# ideal-diode.net
KiCad netlist of a schematic drawn in Altium Designer
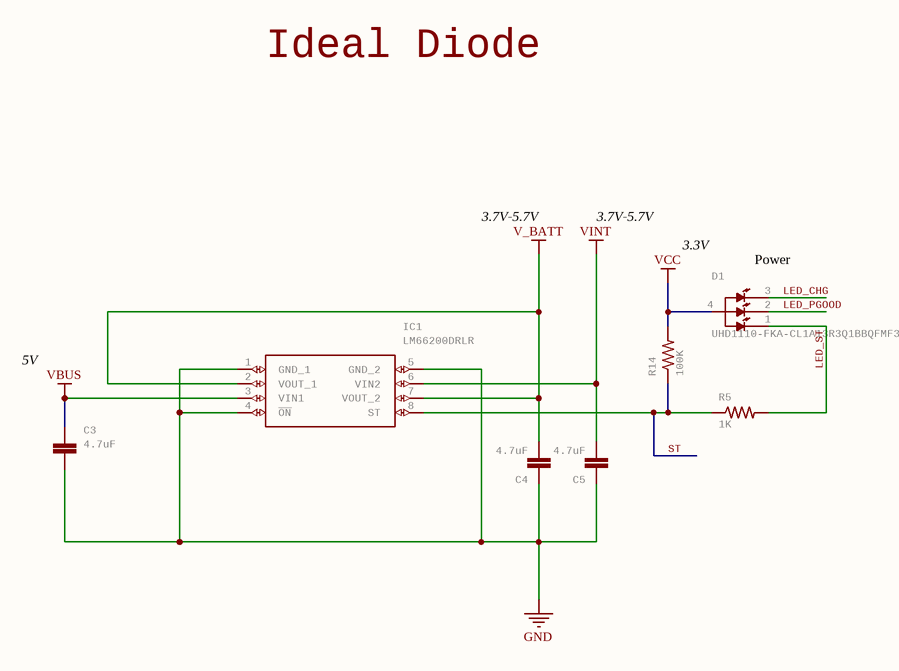
[diagram p0: ideal-diode.SchDoc]

(export (version "E")
  (design (tool "Eeschema 10.0.6"))
  (components
    (comp (ref "C3")
      (value "4.7uF")
      (footprint "0402-CAP")
      (description "CapacitorStandard 0603 ceramic capacitor, and 0.1\" leaded capacitor.")
      (fields (field (name "MPN") "JMK105BBJ475MV-F"))
      (libsource (lib "rt10") (part "CAP0402-CAP"))
    )
    (comp (ref "C4")
      (value "4.7uF")
      (footprint "0402-CAP")
      (description "CapacitorStandard 0603 ceramic capacitor, and 0.1\" leaded capacitor.")
      (fields (field (name "MPN") "JMK105BBJ475MV-F"))
      (libsource (lib "rt10") (part "CAP0402-CAP"))
    )
    (comp (ref "C5")
      (value "4.7uF")
      (footprint "0402-CAP")
      (description "CapacitorStandard 0603 ceramic capacitor, and 0.1\" leaded capacitor.")
      (fields (field (name "MPN") "JMK105BBJ475MV-F"))
      (libsource (lib "rt10") (part "CAP0402-CAP"))
    )
    (comp (ref "D1")
      (value "UHD1110-FKA-CL1A13R3Q1BBQFMF3")
      (footprint "LED_UHD1110-FKA-CL1A13R3Q1BBQFMF3")
      (description "LED RGB SMD, SIZE 1 X 1 mm Check availability")
      (fields (field (name "MF") "Cree Inc.") (field (name "MPN") "UHD1110-FKA-CL1A13r3q1BBQFMF3"))
      (libsource (lib "rt10") (part "UHD1110-FKA-CL1A13R3Q1BBQFMF3"))
    )
    (comp (ref "IC1")
      (value "LM66200DRLR")
      (footprint "SOTFL50P160X60-8N")
      (description "1.6-V to 5.5-V, 40-m, 2.5-A, low-IQ, dual ideal diode   Source:  Datasheet")
      (fields (field (name "MOUSER_PART_NUMBER") "595-LM66200DRLR"))
      (libsource (lib "rt10") (part "LM66200DRLR"))
    )
    (comp (ref "R5")
      (value "1K")
      (footprint "0402-RES")
      (description "ResistorBasic schematic elements and footprints for 0603, 1206, and PTH resistors.")
      (fields (field (name "MPN") "CRCW04021K00FKEDC"))
      (libsource (lib "rt10") (part "RESISTOR0402-RES"))
    )
    (comp (ref "R14")
      (value "100K")
      (footprint "0402-RES")
      (description "ResistorBasic schematic elements and footprints for 0603, 1206, and PTH resistors.")
      (fields (field (name "MPN") "AC0402FR-07100KL"))
      (libsource (lib "rt10") (part "RESISTOR0402-RES"))
    )
  )
  (nets
    (net (code "1") (name "/LED_CHG") (class "Default")
      (node (ref "D1") (pin "3") (pinfunction "RED_3") (pintype "passive"))
    )
    (net (code "2") (name "/LED_PGOOD") (class "Default")
      (node (ref "D1") (pin "2") (pinfunction "GREEN_2") (pintype "passive"))
    )
    (net (code "3") (name "/LED_ST") (class "Default")
      (node (ref "D1") (pin "1") (pinfunction "BLUE_1") (pintype "passive"))
      (node (ref "R5") (pin "2") (pinfunction "2_2") (pintype "passive"))
    )
    (net (code "4") (name "/ST") (class "Default")
      (node (ref "IC1") (pin "8") (pinfunction "ST_8") (pintype "bidirectional"))
      (node (ref "R14") (pin "1") (pinfunction "1_1") (pintype "passive"))
      (node (ref "R5") (pin "1") (pinfunction "1_1") (pintype "passive"))
    )
    (net (code "5") (name "GND") (class "Default")
      (node (ref "C3") (pin "1") (pinfunction "1_1") (pintype "passive"))
      (node (ref "C4") (pin "1") (pinfunction "1_1") (pintype "passive"))
      (node (ref "C5") (pin "1") (pinfunction "1_1") (pintype "passive"))
      (node (ref "IC1") (pin "1") (pinfunction "GND_1_1") (pintype "bidirectional"))
      (node (ref "IC1") (pin "4") (pinfunction "~{ON}_4") (pintype "bidirectional"))
      (node (ref "IC1") (pin "5") (pinfunction "GND_2_5") (pintype "bidirectional"))
    )
    (net (code "6") (name "VBUS") (class "Default")
      (node (ref "C3") (pin "2") (pinfunction "2_2") (pintype "passive"))
      (node (ref "IC1") (pin "3") (pinfunction "VIN1_3") (pintype "bidirectional"))
    )
    (net (code "7") (name "VCC") (class "Default")
      (node (ref "D1") (pin "4") (pinfunction "ANODE_4") (pintype "passive"))
      (node (ref "R14") (pin "2") (pinfunction "2_2") (pintype "passive"))
    )
    (net (code "8") (name "VINT") (class "Default")
      (node (ref "C5") (pin "2") (pinfunction "2_2") (pintype "passive"))
      (node (ref "IC1") (pin "6") (pinfunction "VIN2_6") (pintype "bidirectional"))
    )
    (net (code "9") (name "V_BATT") (class "Default")
      (node (ref "C4") (pin "2") (pinfunction "2_2") (pintype "passive"))
      (node (ref "IC1") (pin "2") (pinfunction "VOUT_1_2") (pintype "bidirectional"))
      (node (ref "IC1") (pin "7") (pinfunction "VOUT_2_7") (pintype "bidirectional"))
    )
  )
)
